# tinybord.net
KiCad netlist of a schematic drawn in Altium Designer
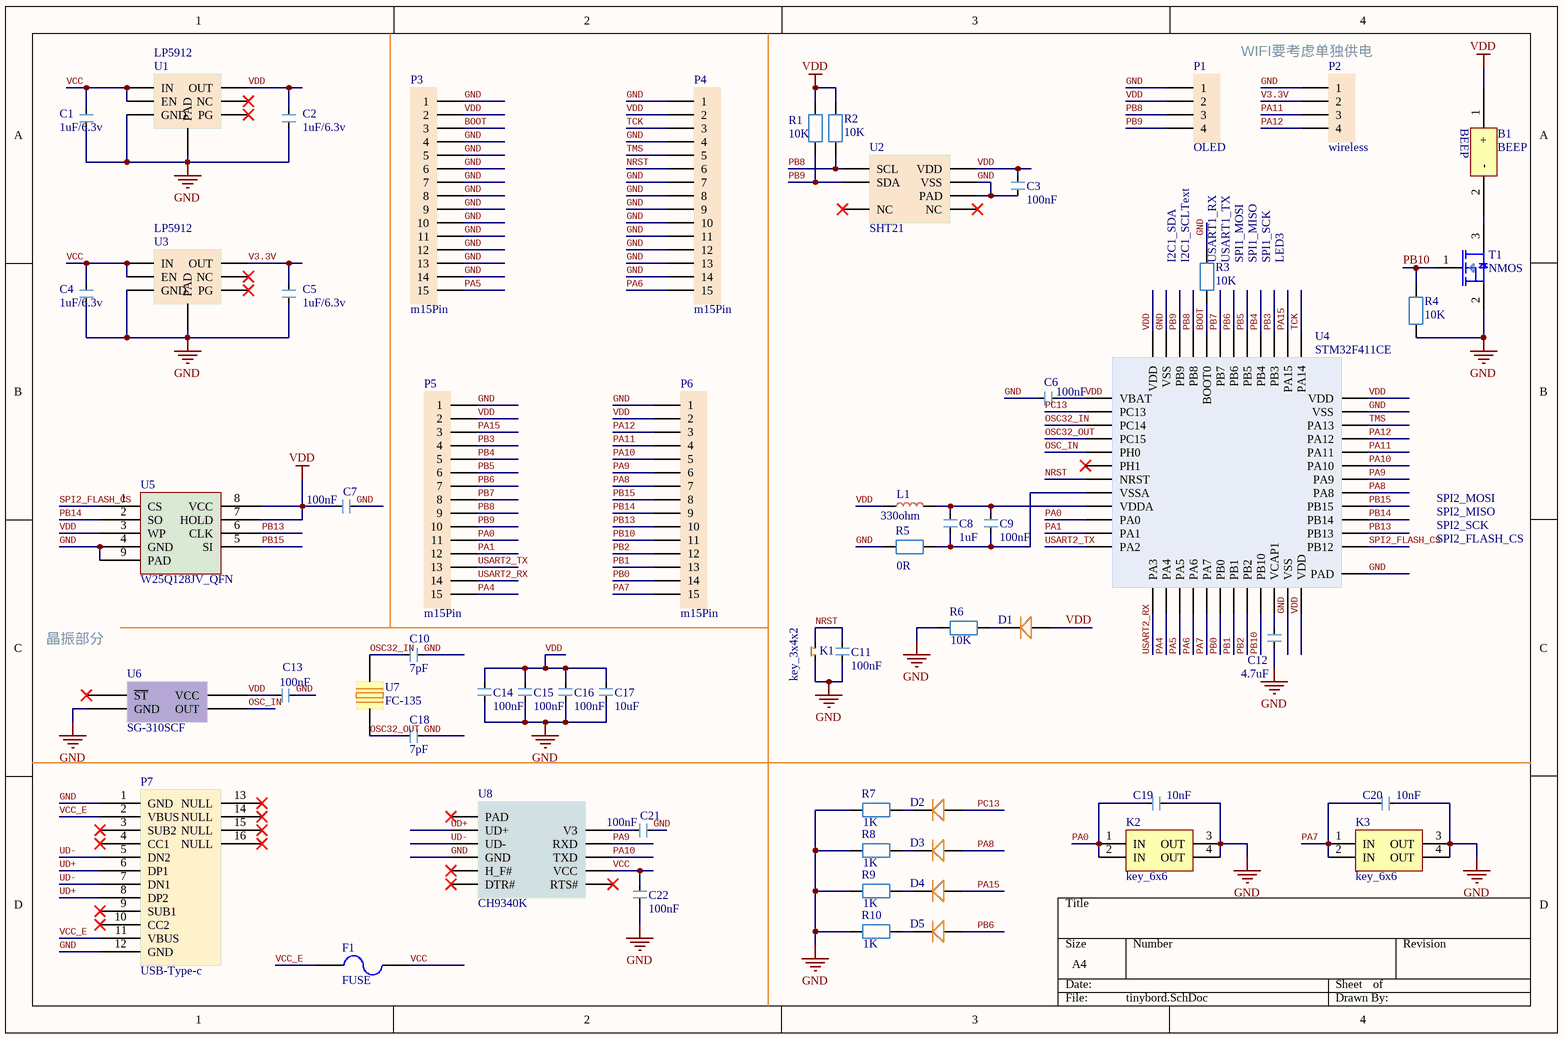
[diagram p0: tinybord.SchDoc]

(export (version "E")
  (design (tool "Eeschema 10.0.6"))
  (components
    (comp (ref "B1")
      (value "BEEP")
      (footprint "BEEP0905")
      (description "12*6")
      (libsource (lib "DemoSchlib") (part "BEEP"))
    )
    (comp (ref "C1")
      (value "1uF/6.3v")
      (footprint "C0603")
      (description "陶瓷电容")
      (fields (field (name "Comment") "C0603"))
      (libsource (lib "DemoSchlib") (part "C0603"))
    )
    (comp (ref "C2")
      (value "1uF/6.3v")
      (footprint "C0603")
      (description "陶瓷电容")
      (fields (field (name "Comment") "C0603"))
      (libsource (lib "DemoSchlib") (part "C0603"))
    )
    (comp (ref "C3")
      (value "100nF")
      (footprint "C0603")
      (description "陶瓷电容")
      (fields (field (name "Comment") "C0603"))
      (libsource (lib "DemoSchlib") (part "C0603"))
    )
    (comp (ref "C4")
      (value "1uF/6.3v")
      (footprint "C0603")
      (description "陶瓷电容")
      (fields (field (name "Comment") "C0603"))
      (libsource (lib "DemoSchlib") (part "C0603"))
    )
    (comp (ref "C5")
      (value "1uF/6.3v")
      (footprint "C0603")
      (description "陶瓷电容")
      (fields (field (name "Comment") "C0603"))
      (libsource (lib "DemoSchlib") (part "C0603"))
    )
    (comp (ref "C6")
      (value "100nF")
      (footprint "C0603")
      (description "陶瓷电容")
      (fields (field (name "Comment") "C0603"))
      (libsource (lib "DemoSchlib") (part "C0603"))
    )
    (comp (ref "C7")
      (value "100nF")
      (footprint "C0603")
      (description "陶瓷电容")
      (fields (field (name "Comment") "C0603"))
      (libsource (lib "DemoSchlib") (part "C0603"))
    )
    (comp (ref "C8")
      (value "1uF")
      (footprint "C0603")
      (description "陶瓷电容")
      (fields (field (name "Comment") "C0603"))
      (libsource (lib "DemoSchlib") (part "C0603"))
    )
    (comp (ref "C9")
      (value "100nF")
      (footprint "C0603")
      (description "陶瓷电容")
      (fields (field (name "Comment") "C0603"))
      (libsource (lib "DemoSchlib") (part "C0603"))
    )
    (comp (ref "C10")
      (value "7pF")
      (footprint "C0603")
      (description "陶瓷电容")
      (fields (field (name "Comment") "C0603"))
      (libsource (lib "DemoSchlib") (part "C0603"))
    )
    (comp (ref "C11")
      (value "100nF")
      (footprint "C0603")
      (description "陶瓷电容")
      (fields (field (name "Comment") "C0603"))
      (libsource (lib "DemoSchlib") (part "C0603"))
    )
    (comp (ref "C12")
      (value "4.7uF")
      (footprint "C0603")
      (description "陶瓷电容")
      (fields (field (name "Comment") "C0603"))
      (libsource (lib "DemoSchlib") (part "C0603"))
    )
    (comp (ref "C13")
      (value "100nF")
      (footprint "C0603")
      (description "陶瓷电容")
      (fields (field (name "Comment") "C0603"))
      (libsource (lib "DemoSchlib") (part "C0603"))
    )
    (comp (ref "C14")
      (value "100nF")
      (footprint "C0603")
      (description "陶瓷电容")
      (fields (field (name "Comment") "C0603"))
      (libsource (lib "DemoSchlib") (part "C0603"))
    )
    (comp (ref "C15")
      (value "100nF")
      (footprint "C0603")
      (description "陶瓷电容")
      (fields (field (name "Comment") "C0603"))
      (libsource (lib "DemoSchlib") (part "C0603"))
    )
    (comp (ref "C16")
      (value "100nF")
      (footprint "C0603")
      (description "陶瓷电容")
      (fields (field (name "Comment") "C0603"))
      (libsource (lib "DemoSchlib") (part "C0603"))
    )
    (comp (ref "C17")
      (value "10uF")
      (footprint "C0603")
      (description "陶瓷电容")
      (fields (field (name "Comment") "C0603"))
      (libsource (lib "DemoSchlib") (part "C0603"))
    )
    (comp (ref "C18")
      (value "7pF")
      (footprint "C0603")
      (description "陶瓷电容")
      (fields (field (name "Comment") "C0603"))
      (libsource (lib "DemoSchlib") (part "C0603"))
    )
    (comp (ref "C19")
      (value "10nF")
      (footprint "C0603")
      (description "陶瓷电容")
      (fields (field (name "Comment") "C0603"))
      (libsource (lib "DemoSchlib") (part "C0603"))
    )
    (comp (ref "C20")
      (value "10nF")
      (footprint "C0603")
      (description "陶瓷电容")
      (fields (field (name "Comment") "C0603"))
      (libsource (lib "DemoSchlib") (part "C0603"))
    )
    (comp (ref "C21")
      (value "100nF")
      (footprint "C0603")
      (description "陶瓷电容")
      (fields (field (name "Comment") "C0603"))
      (libsource (lib "DemoSchlib") (part "C0603"))
    )
    (comp (ref "C22")
      (value "100nF")
      (footprint "C0603")
      (description "陶瓷电容")
      (fields (field (name "Comment") "C0603"))
      (libsource (lib "DemoSchlib") (part "C0603"))
    )
    (comp (ref "D1")
      (value "L0603")
      (footprint "led0603")
      (description "LED")
      (libsource (lib "DemoSchlib") (part "L0603"))
    )
    (comp (ref "D2")
      (value "L0603")
      (footprint "led0603")
      (description "LED")
      (libsource (lib "DemoSchlib") (part "L0603"))
    )
    (comp (ref "D3")
      (value "L0603")
      (footprint "led0603")
      (description "LED")
      (libsource (lib "DemoSchlib") (part "L0603"))
    )
    (comp (ref "D4")
      (value "L0603")
      (footprint "led0603")
      (description "LED")
      (libsource (lib "DemoSchlib") (part "L0603"))
    )
    (comp (ref "D5")
      (value "L0603")
      (footprint "led0603")
      (description "LED")
      (libsource (lib "DemoSchlib") (part "L0603"))
    )
    (comp (ref "F1")
      (value "FUSE")
      (footprint "R0603")
      (description "PTC 1812")
      (libsource (lib "DemoSchlib") (part "PTC0603"))
    )
    (comp (ref "K1")
      (value "key_3x4x2")
      (footprint "Key 3x4x2")
      (description "贴片按键")
      (libsource (lib "DemoSchlib") (part "key_3x4x2"))
    )
    (comp (ref "K2")
      (value "key_6x6")
      (footprint "Key 6x6")
      (description "贴片按键")
      (libsource (lib "DemoSchlib") (part "key_6x6"))
    )
    (comp (ref "K3")
      (value "key_6x6")
      (footprint "Key 6x6")
      (description "贴片按键")
      (libsource (lib "DemoSchlib") (part "key_6x6"))
    )
    (comp (ref "L1")
      (value "330ohm")
      (footprint "B0603")
      (description "磁珠")
      (fields (field (name "Comment") "B0603"))
      (libsource (lib "DemoSchlib") (part "B0603"))
    )
    (comp (ref "P1")
      (value "OLED")
      (footprint "4x1 header")
      (description "1x4pin 1.27mm")
      (libsource (lib "DemoSchlib") (part "m4Pin"))
    )
    (comp (ref "P2")
      (value "wireless")
      (footprint "4x1 header")
      (description "1x4pin 1.27mm")
      (libsource (lib "DemoSchlib") (part "m4Pin"))
    )
    (comp (ref "P3")
      (value "m15Pin")
      (footprint "15x1 header")
      (description "1x4pin 1.27mm")
      (libsource (lib "DemoSchlib") (part "m15Pin"))
    )
    (comp (ref "P4")
      (value "m15Pin")
      (footprint "15x1 header")
      (description "1x4pin 1.27mm")
      (libsource (lib "") (part "m15Pin_1"))
    )
    (comp (ref "P5")
      (value "m15Pin")
      (footprint "15x1 header")
      (description "1x4pin 1.27mm")
      (libsource (lib "DemoSchlib") (part "m15Pin"))
    )
    (comp (ref "P6")
      (value "m15Pin")
      (footprint "15x1 header")
      (description "1x4pin 1.27mm")
      (libsource (lib "") (part "m15Pin_1"))
    )
    (comp (ref "P7")
      (value "USB-Type-c")
      (footprint "USB-TYPE-C")
      (description "use typec 16p")
      (libsource (lib "DemoSchlib") (part "USB-Type-c"))
    )
    (comp (ref "R1")
      (value "10K")
      (footprint "R0603")
      (description "电阻")
      (fields (field (name "Comment") "R0603"))
      (libsource (lib "DemoSchlib") (part "R0603"))
    )
    (comp (ref "R2")
      (value "10K")
      (footprint "R0603")
      (description "电阻")
      (fields (field (name "Comment") "R0603"))
      (libsource (lib "DemoSchlib") (part "R0603"))
    )
    (comp (ref "R3")
      (value "10K")
      (footprint "R0603")
      (description "电阻")
      (fields (field (name "Comment") "R0603"))
      (libsource (lib "DemoSchlib") (part "R0603"))
    )
    (comp (ref "R4")
      (value "10K")
      (footprint "R0603")
      (description "电阻")
      (fields (field (name "Comment") "R0603"))
      (libsource (lib "DemoSchlib") (part "R0603"))
    )
    (comp (ref "R5")
      (value "0R")
      (footprint "R0603")
      (description "电阻")
      (fields (field (name "Comment") "R0603"))
      (libsource (lib "DemoSchlib") (part "R0603"))
    )
    (comp (ref "R6")
      (value "10K")
      (footprint "R0603")
      (description "电阻")
      (fields (field (name "Comment") "R0603"))
      (libsource (lib "DemoSchlib") (part "R0603"))
    )
    (comp (ref "R7")
      (value "1K")
      (footprint "R0603")
      (description "电阻")
      (fields (field (name "Comment") "R0603"))
      (libsource (lib "DemoSchlib") (part "R0603"))
    )
    (comp (ref "R8")
      (value "1K")
      (footprint "R0603")
      (description "电阻")
      (fields (field (name "Comment") "R0603"))
      (libsource (lib "DemoSchlib") (part "R0603"))
    )
    (comp (ref "R9")
      (value "1K")
      (footprint "R0603")
      (description "电阻")
      (fields (field (name "Comment") "R0603"))
      (libsource (lib "DemoSchlib") (part "R0603"))
    )
    (comp (ref "R10")
      (value "1K")
      (footprint "R0603")
      (description "电阻")
      (fields (field (name "Comment") "R0603"))
      (libsource (lib "DemoSchlib") (part "R0603"))
    )
    (comp (ref "T1")
      (value "NMOS")
      (footprint "NMOS-BSH103")
      (description "infineon P-Chanel")
      (libsource (lib "DemoSchlib") (part "NMOS-BSH103"))
    )
    (comp (ref "U1")
      (value "LP5912")
      (footprint "LP5912")
      (description "LDO")
      (libsource (lib "DemoSchlib") (part "LP5912"))
    )
    (comp (ref "U2")
      (value "SHT21")
      (footprint "SHT21")
      (description "温湿度传感器")
      (libsource (lib "DemoSchlib") (part "SHT21"))
    )
    (comp (ref "U3")
      (value "LP5912")
      (footprint "LP5912")
      (description "LDO")
      (libsource (lib "DemoSchlib") (part "LP5912"))
    )
    (comp (ref "U4")
      (value "STM32F411CE")
      (footprint "STM32F411CE QFN")
      (description "STM32F411 QFN48PIN")
      (libsource (lib "DemoSchlib") (part "STM32F411CE"))
    )
    (comp (ref "U5")
      (value "W25Q128JV_QFN")
      (footprint "W25Q64 QFN")
      (description "flash")
      (libsource (lib "DemoSchlib") (part "W25Q128JV_QFN"))
    )
    (comp (ref "U6")
      (value "SG-310SCF")
      (footprint "SG-310SCF")
      (description "有源晶振3225")
      (libsource (lib "DemoSchlib") (part "SG-310SCF"))
    )
    (comp (ref "U7")
      (value "FC-135")
      (footprint "FC-135")
      (description "32.768K无源晶振")
      (libsource (lib "DemoSchlib") (part "FC-135"))
    )
    (comp (ref "U8")
      (value "CH9340K")
      (footprint "CH9340")
      (description "USB转串口")
      (libsource (lib "DemoSchlib") (part "CH9340K"))
    )
  )
  (nets
    (net (code "1") (name "/BOOT") (class "Default")
      (node (ref "P3") (pin "3") (pinfunction "3_3") (pintype "passive"))
      (node (ref "R3") (pin "1") (pintype "passive"))
      (node (ref "U4") (pin "44") (pinfunction "BOOT0_44") (pintype "passive"))
    )
    (net (code "2") (name "/NRST") (class "Default")
      (node (ref "C11") (pin "2") (pintype "passive"))
      (node (ref "K1") (pin "2") (pintype "passive"))
      (node (ref "P4") (pin "6") (pinfunction "6_6") (pintype "passive"))
      (node (ref "U4") (pin "7") (pinfunction "NRST_7") (pintype "passive"))
    )
    (net (code "3") (name "/OSC32_IN") (class "Default")
      (node (ref "C10") (pin "2") (pintype "passive"))
      (node (ref "U4") (pin "3") (pinfunction "PC14_3") (pintype "passive"))
      (node (ref "U7") (pin "2") (pintype "passive"))
    )
    (net (code "4") (name "/OSC32_OUT") (class "Default")
      (node (ref "C18") (pin "2") (pintype "passive"))
      (node (ref "U4") (pin "4") (pinfunction "PC15_4") (pintype "passive"))
      (node (ref "U7") (pin "1") (pintype "passive"))
    )
    (net (code "5") (name "/OSC_IN") (class "Default")
      (node (ref "U4") (pin "5") (pinfunction "PH0_5") (pintype "passive"))
      (node (ref "U6") (pin "3") (pinfunction "OUT_3") (pintype "passive"))
    )
    (net (code "6") (name "/PA0") (class "Default")
      (node (ref "C19") (pin "2") (pintype "passive"))
      (node (ref "K2") (pin "1") (pinfunction "IN_1") (pintype "passive"))
      (node (ref "K2") (pin "2") (pinfunction "IN_2") (pintype "passive"))
      (node (ref "P5") (pin "11") (pinfunction "11_11") (pintype "passive"))
      (node (ref "U4") (pin "10") (pinfunction "PA0_10") (pintype "passive"))
    )
    (net (code "7") (name "/PA1") (class "Default")
      (node (ref "P5") (pin "12") (pinfunction "12_12") (pintype "passive"))
      (node (ref "U4") (pin "11") (pinfunction "PA1_11") (pintype "passive"))
    )
    (net (code "8") (name "/PA4") (class "Default")
      (node (ref "P5") (pin "15") (pinfunction "15_15") (pintype "passive"))
      (node (ref "U4") (pin "14") (pinfunction "PA4_14") (pintype "passive"))
    )
    (net (code "9") (name "/PA5") (class "Default")
      (node (ref "P3") (pin "15") (pinfunction "15_15") (pintype "passive"))
      (node (ref "U4") (pin "15") (pinfunction "PA5_15") (pintype "passive"))
    )
    (net (code "10") (name "/PA6") (class "Default")
      (node (ref "P4") (pin "15") (pinfunction "15_15") (pintype "passive"))
      (node (ref "U4") (pin "16") (pinfunction "PA6_16") (pintype "passive"))
    )
    (net (code "11") (name "/PA7") (class "Default")
      (node (ref "C20") (pin "2") (pintype "passive"))
      (node (ref "K3") (pin "1") (pinfunction "IN_1") (pintype "passive"))
      (node (ref "K3") (pin "2") (pinfunction "IN_2") (pintype "passive"))
      (node (ref "P6") (pin "15") (pinfunction "15_15") (pintype "passive"))
      (node (ref "U4") (pin "17") (pinfunction "PA7_17") (pintype "passive"))
    )
    (net (code "12") (name "/PA8") (class "Default")
      (node (ref "D3") (pin "2") (pintype "passive"))
      (node (ref "P6") (pin "7") (pinfunction "7_7") (pintype "passive"))
      (node (ref "U4") (pin "29") (pinfunction "PA8_29") (pintype "passive"))
    )
    (net (code "13") (name "/PA9") (class "Default")
      (node (ref "P6") (pin "6") (pinfunction "6_6") (pintype "passive"))
      (node (ref "U4") (pin "30") (pinfunction "PA9_30") (pintype "passive"))
      (node (ref "U8") (pin "9") (pinfunction "RXD_9") (pintype "passive"))
    )
    (net (code "14") (name "/PA10") (class "Default")
      (node (ref "P6") (pin "5") (pinfunction "5_5") (pintype "passive"))
      (node (ref "U4") (pin "31") (pinfunction "PA10_31") (pintype "passive"))
      (node (ref "U8") (pin "8") (pinfunction "TXD_8") (pintype "passive"))
    )
    (net (code "15") (name "/PA11") (class "Default")
      (node (ref "P2") (pin "3") (pinfunction "3_3") (pintype "passive"))
      (node (ref "P6") (pin "4") (pinfunction "4_4") (pintype "passive"))
      (node (ref "U4") (pin "32") (pinfunction "PA11_32") (pintype "passive"))
    )
    (net (code "16") (name "/PA12") (class "Default")
      (node (ref "P2") (pin "4") (pinfunction "4_4") (pintype "passive"))
      (node (ref "P6") (pin "3") (pinfunction "3_3") (pintype "passive"))
      (node (ref "U4") (pin "33") (pinfunction "PA12_33") (pintype "passive"))
    )
    (net (code "17") (name "/PA15") (class "Default")
      (node (ref "D4") (pin "2") (pintype "passive"))
      (node (ref "P5") (pin "3") (pinfunction "3_3") (pintype "passive"))
      (node (ref "U4") (pin "38") (pinfunction "PA15_38") (pintype "passive"))
    )
    (net (code "18") (name "/PB0") (class "Default")
      (node (ref "P6") (pin "14") (pinfunction "14_14") (pintype "passive"))
      (node (ref "U4") (pin "18") (pinfunction "PB0_18") (pintype "passive"))
    )
    (net (code "19") (name "/PB1") (class "Default")
      (node (ref "P6") (pin "13") (pinfunction "13_13") (pintype "passive"))
      (node (ref "U4") (pin "19") (pinfunction "PB1_19") (pintype "passive"))
    )
    (net (code "20") (name "/PB2") (class "Default")
      (node (ref "P6") (pin "12") (pinfunction "12_12") (pintype "passive"))
      (node (ref "U4") (pin "20") (pinfunction "PB2_20") (pintype "passive"))
    )
    (net (code "21") (name "/PB3") (class "Default")
      (node (ref "P5") (pin "4") (pinfunction "4_4") (pintype "passive"))
      (node (ref "U4") (pin "39") (pinfunction "PB3_39") (pintype "passive"))
    )
    (net (code "22") (name "/PB4") (class "Default")
      (node (ref "P5") (pin "5") (pinfunction "5_5") (pintype "passive"))
      (node (ref "U4") (pin "40") (pinfunction "PB4_40") (pintype "passive"))
    )
    (net (code "23") (name "/PB5") (class "Default")
      (node (ref "P5") (pin "6") (pinfunction "6_6") (pintype "passive"))
      (node (ref "U4") (pin "41") (pinfunction "PB5_41") (pintype "passive"))
    )
    (net (code "24") (name "/PB6") (class "Default")
      (node (ref "D5") (pin "2") (pintype "passive"))
      (node (ref "P5") (pin "7") (pinfunction "7_7") (pintype "passive"))
      (node (ref "U4") (pin "42") (pinfunction "PB6_42") (pintype "passive"))
    )
    (net (code "25") (name "/PB7") (class "Default")
      (node (ref "P5") (pin "8") (pinfunction "8_8") (pintype "passive"))
      (node (ref "U4") (pin "43") (pinfunction "PB7_43") (pintype "passive"))
    )
    (net (code "26") (name "/PB8") (class "Default")
      (node (ref "P1") (pin "3") (pinfunction "3_3") (pintype "passive"))
      (node (ref "P5") (pin "9") (pinfunction "9_9") (pintype "passive"))
      (node (ref "R2") (pin "1") (pintype "passive"))
      (node (ref "U2") (pin "6") (pinfunction "SCL_6") (pintype "passive"))
      (node (ref "U4") (pin "45") (pinfunction "PB8_45") (pintype "passive"))
    )
    (net (code "27") (name "/PB9") (class "Default")
      (node (ref "P1") (pin "4") (pinfunction "4_4") (pintype "passive"))
      (node (ref "P5") (pin "10") (pinfunction "10_10") (pintype "passive"))
      (node (ref "R1") (pin "1") (pintype "passive"))
      (node (ref "U2") (pin "1") (pinfunction "SDA_1") (pintype "passive"))
      (node (ref "U4") (pin "46") (pinfunction "PB9_46") (pintype "passive"))
    )
    (net (code "28") (name "/PB10") (class "Default")
      (node (ref "P6") (pin "11") (pinfunction "11_11") (pintype "passive"))
      (node (ref "R4") (pin "2") (pintype "passive"))
      (node (ref "T1") (pin "1") (pinfunction "G_1") (pintype "passive"))
      (node (ref "U4") (pin "21") (pinfunction "PB10_21") (pintype "passive"))
    )
    (net (code "29") (name "/PB13") (class "Default")
      (node (ref "P6") (pin "10") (pinfunction "10_10") (pintype "passive"))
      (node (ref "U4") (pin "26") (pinfunction "PB13_26") (pintype "passive"))
      (node (ref "U5") (pin "6") (pinfunction "CLK_6") (pintype "passive"))
    )
    (net (code "30") (name "/PB14") (class "Default")
      (node (ref "P6") (pin "9") (pinfunction "9_9") (pintype "passive"))
      (node (ref "U4") (pin "27") (pinfunction "PB14_27") (pintype "passive"))
      (node (ref "U5") (pin "2") (pinfunction "SO_2") (pintype "passive"))
    )
    (net (code "31") (name "/PB15") (class "Default")
      (node (ref "P6") (pin "8") (pinfunction "8_8") (pintype "passive"))
      (node (ref "U4") (pin "28") (pinfunction "PB15_28") (pintype "passive"))
      (node (ref "U5") (pin "5") (pinfunction "SI_5") (pintype "passive"))
    )
    (net (code "32") (name "/PC13") (class "Default")
      (node (ref "D2") (pin "2") (pintype "passive"))
      (node (ref "U4") (pin "2") (pinfunction "PC13_2") (pintype "passive"))
    )
    (net (code "33") (name "/SPI2_FLASH_CS") (class "Default")
      (node (ref "U4") (pin "25") (pinfunction "PB12_25") (pintype "passive"))
      (node (ref "U5") (pin "1") (pinfunction "CS_1") (pintype "passive"))
    )
    (net (code "34") (name "/TCK") (class "Default")
      (node (ref "P4") (pin "3") (pinfunction "3_3") (pintype "passive"))
      (node (ref "U4") (pin "37") (pinfunction "PA14_37") (pintype "passive"))
    )
    (net (code "35") (name "/TMS") (class "Default")
      (node (ref "P4") (pin "5") (pinfunction "5_5") (pintype "passive"))
      (node (ref "U4") (pin "34") (pinfunction "PA13_34") (pintype "passive"))
    )
    (net (code "36") (name "/UD+") (class "Default")
      (node (ref "P7") (pin "6") (pinfunction "DP1_6") (pintype "passive"))
      (node (ref "P7") (pin "8") (pinfunction "DP2_8") (pintype "passive"))
      (node (ref "U8") (pin "1") (pinfunction "UD+_1") (pintype "passive"))
    )
    (net (code "37") (name "/UD-") (class "Default")
      (node (ref "P7") (pin "5") (pinfunction "DN2_5") (pintype "passive"))
      (node (ref "P7") (pin "7") (pinfunction "DN1_7") (pintype "passive"))
      (node (ref "U8") (pin "2") (pinfunction "UD-_2") (pintype "passive"))
    )
    (net (code "38") (name "/USART2_RX") (class "Default")
      (node (ref "P5") (pin "14") (pinfunction "14_14") (pintype "passive"))
      (node (ref "U4") (pin "13") (pinfunction "PA3_13") (pintype "passive"))
    )
    (net (code "39") (name "/USART2_TX") (class "Default")
      (node (ref "P5") (pin "13") (pinfunction "13_13") (pintype "passive"))
      (node (ref "U4") (pin "12") (pinfunction "PA2_12") (pintype "passive"))
    )
    (net (code "40") (name "/V3.3V") (class "Default")
      (node (ref "C5") (pin "2") (pintype "passive"))
      (node (ref "P2") (pin "2") (pinfunction "2_2") (pintype "passive"))
      (node (ref "U3") (pin "1") (pinfunction "OUT_1") (pintype "passive"))
    )
    (net (code "41") (name "/VCC") (class "Default")
      (node (ref "C1") (pin "2") (pintype "passive"))
      (node (ref "C22") (pin "2") (pintype "passive"))
      (node (ref "C4") (pin "2") (pintype "passive"))
      (node (ref "F1") (pin "2") (pinfunction "2_2") (pintype "passive"))
      (node (ref "U1") (pin "4") (pinfunction "EN_4") (pintype "passive"))
      (node (ref "U1") (pin "6") (pinfunction "IN_6") (pintype "passive"))
      (node (ref "U3") (pin "4") (pinfunction "EN_4") (pintype "passive"))
      (node (ref "U3") (pin "6") (pinfunction "IN_6") (pintype "passive"))
      (node (ref "U8") (pin "7") (pinfunction "VCC_7") (pintype "passive"))
    )
    (net (code "42") (name "/VCC_E") (class "Default")
      (node (ref "F1") (pin "1") (pinfunction "1_1") (pintype "passive"))
      (node (ref "P7") (pin "11") (pinfunction "VBUS_11") (pintype "passive"))
      (node (ref "P7") (pin "2") (pinfunction "VBUS_2") (pintype "passive"))
    )
    (net (code "43") (name "GND") (class "Default")
      (node (ref "C1") (pin "1") (pintype "passive"))
      (node (ref "C10") (pin "1") (pintype "passive"))
      (node (ref "C11") (pin "1") (pintype "passive"))
      (node (ref "C12") (pin "1") (pintype "passive"))
      (node (ref "C13") (pin "2") (pintype "passive"))
      (node (ref "C14") (pin "1") (pintype "passive"))
      (node (ref "C15") (pin "1") (pintype "passive"))
      (node (ref "C16") (pin "1") (pintype "passive"))
      (node (ref "C17") (pin "1") (pintype "passive"))
      (node (ref "C18") (pin "1") (pintype "passive"))
      (node (ref "C19") (pin "1") (pintype "passive"))
      (node (ref "C2") (pin "1") (pintype "passive"))
      (node (ref "C20") (pin "1") (pintype "passive"))
      (node (ref "C21") (pin "2") (pintype "passive"))
      (node (ref "C22") (pin "1") (pintype "passive"))
      (node (ref "C3") (pin "1") (pintype "passive"))
      (node (ref "C4") (pin "1") (pintype "passive"))
      (node (ref "C5") (pin "1") (pintype "passive"))
      (node (ref "C6") (pin "1") (pintype "passive"))
      (node (ref "C7") (pin "2") (pintype "passive"))
      (node (ref "K1") (pin "1") (pintype "passive"))
      (node (ref "K2") (pin "3") (pinfunction "OUT_3") (pintype "passive"))
      (node (ref "K2") (pin "4") (pinfunction "OUT_4") (pintype "passive"))
      (node (ref "K3") (pin "3") (pinfunction "OUT_3") (pintype "passive"))
      (node (ref "K3") (pin "4") (pinfunction "OUT_4") (pintype "passive"))
      (node (ref "P1") (pin "1") (pinfunction "1_1") (pintype "passive"))
      (node (ref "P2") (pin "1") (pinfunction "1_1") (pintype "passive"))
      (node (ref "P3") (pin "1") (pinfunction "1_1") (pintype "passive"))
      (node (ref "P3") (pin "10") (pinfunction "10_10") (pintype "passive"))
      (node (ref "P3") (pin "11") (pinfunction "11_11") (pintype "passive"))
      (node (ref "P3") (pin "12") (pinfunction "12_12") (pintype "passive"))
      (node (ref "P3") (pin "13") (pinfunction "13_13") (pintype "passive"))
      (node (ref "P3") (pin "14") (pinfunction "14_14") (pintype "passive"))
      (node (ref "P3") (pin "4") (pinfunction "4_4") (pintype "passive"))
      (node (ref "P3") (pin "5") (pinfunction "5_5") (pintype "passive"))
      (node (ref "P3") (pin "6") (pinfunction "6_6") (pintype "passive"))
      (node (ref "P3") (pin "7") (pinfunction "7_7") (pintype "passive"))
      (node (ref "P3") (pin "8") (pinfunction "8_8") (pintype "passive"))
      (node (ref "P3") (pin "9") (pinfunction "9_9") (pintype "passive"))
      (node (ref "P4") (pin "1") (pinfunction "1_1") (pintype "passive"))
      (node (ref "P4") (pin "10") (pinfunction "10_10") (pintype "passive"))
      (node (ref "P4") (pin "11") (pinfunction "11_11") (pintype "passive"))
      (node (ref "P4") (pin "12") (pinfunction "12_12") (pintype "passive"))
      (node (ref "P4") (pin "13") (pinfunction "13_13") (pintype "passive"))
      (node (ref "P4") (pin "14") (pinfunction "14_14") (pintype "passive"))
      (node (ref "P4") (pin "4") (pinfunction "4_4") (pintype "passive"))
      (node (ref "P4") (pin "7") (pinfunction "7_7") (pintype "passive"))
      (node (ref "P4") (pin "8") (pinfunction "8_8") (pintype "passive"))
      (node (ref "P4") (pin "9") (pinfunction "9_9") (pintype "passive"))
      (node (ref "P5") (pin "1") (pinfunction "1_1") (pintype "passive"))
      (node (ref "P6") (pin "1") (pinfunction "1_1") (pintype "passive"))
      (node (ref "P7") (pin "1") (pinfunction "GND_1") (pintype "passive"))
      (node (ref "P7") (pin "12") (pinfunction "GND_12") (pintype "passive"))
      (node (ref "R10") (pin "1") (pintype "passive"))
      (node (ref "R3") (pin "2") (pintype "passive"))
      (node (ref "R4") (pin "1") (pintype "passive"))
      (node (ref "R5") (pin "1") (pintype "passive"))
      (node (ref "R6") (pin "1") (pintype "passive"))
      (node (ref "R7") (pin "1") (pintype "passive"))
      (node (ref "R8") (pin "1") (pintype "passive"))
      (node (ref "R9") (pin "1") (pintype "passive"))
      (node (ref "T1") (pin "2") (pinfunction "S_2") (pintype "passive"))
      (node (ref "U1") (pin "5") (pinfunction "GND_5") (pintype "passive"))
      (node (ref "U1") (pin "7") (pinfunction "PAD_7") (pintype "passive"))
      (node (ref "U2") (pin "2") (pinfunction "VSS_2") (pintype "passive"))
      (node (ref "U2") (pin "7") (pinfunction "PAD_7") (pintype "passive"))
      (node (ref "U3") (pin "5") (pinfunction "GND_5") (pintype "passive"))
      (node (ref "U3") (pin "7") (pinfunction "PAD_7") (pintype "passive"))
      (node (ref "U4") (pin "23") (pinfunction "VSS_23") (pintype "passive"))
      (node (ref "U4") (pin "35") (pinfunction "VSS_35") (pintype "passive"))
      (node (ref "U4") (pin "47") (pinfunction "VSS_47") (pintype "passive"))
      (node (ref "U4") (pin "49") (pinfunction "PAD_49") (pintype "passive"))
      (node (ref "U5") (pin "4") (pinfunction "GND_4") (pintype "passive"))
      (node (ref "U5") (pin "9") (pinfunction "PAD_9") (pintype "passive"))
      (node (ref "U6") (pin "2") (pinfunction "GND_2") (pintype "passive"))
      (node (ref "U8") (pin "3") (pinfunction "GND_3") (pintype "passive"))
    )
    (net (code "44") (name "Net-(B1--)") (class "Default")
      (node (ref "B1") (pin "2") (pinfunction "-_2") (pintype "passive"))
      (node (ref "T1") (pin "3") (pinfunction "D_3") (pintype "passive"))
    )
    (net (code "45") (name "Net-(D1-Pad1)") (class "Default")
      (node (ref "D1") (pin "1") (pintype "passive"))
      (node (ref "R6") (pin "2") (pintype "passive"))
    )
    (net (code "46") (name "Net-(D2-Pad1)") (class "Default")
      (node (ref "D2") (pin "1") (pintype "passive"))
      (node (ref "R7") (pin "2") (pintype "passive"))
    )
    (net (code "47") (name "Net-(D3-Pad1)") (class "Default")
      (node (ref "D3") (pin "1") (pintype "passive"))
      (node (ref "R8") (pin "2") (pintype "passive"))
    )
    (net (code "48") (name "Net-(D4-Pad1)") (class "Default")
      (node (ref "D4") (pin "1") (pintype "passive"))
      (node (ref "R9") (pin "2") (pintype "passive"))
    )
    (net (code "49") (name "Net-(D5-Pad1)") (class "Default")
      (node (ref "D5") (pin "1") (pintype "passive"))
      (node (ref "R10") (pin "2") (pintype "passive"))
    )
    (net (code "50") (name "Net-(U4-VCAP1)") (class "Default")
      (node (ref "C12") (pin "2") (pintype "passive"))
      (node (ref "U4") (pin "22") (pinfunction "VCAP1_22") (pintype "passive"))
    )
    (net (code "51") (name "Net-(U4-VDDA)") (class "Default")
      (node (ref "C8") (pin "2") (pintype "passive"))
      (node (ref "C9") (pin "2") (pintype "passive"))
      (node (ref "L1") (pin "2") (pintype "passive"))
      (node (ref "U4") (pin "9") (pinfunction "VDDA_9") (pintype "passive"))
    )
    (net (code "52") (name "Net-(U4-VSSA)") (class "Default")
      (node (ref "C8") (pin "1") (pintype "passive"))
      (node (ref "C9") (pin "1") (pintype "passive"))
      (node (ref "R5") (pin "2") (pintype "passive"))
      (node (ref "U4") (pin "8") (pinfunction "VSSA_8") (pintype "passive"))
    )
    (net (code "53") (name "Net-(U8-V3)") (class "Default")
      (node (ref "C21") (pin "1") (pintype "passive"))
      (node (ref "U8") (pin "10") (pinfunction "V3_10") (pintype "passive"))
    )
    (net (code "54") (name "VDD") (class "Default")
      (node (ref "B1") (pin "1") (pinfunction "+_1") (pintype "passive"))
      (node (ref "C13") (pin "1") (pintype "passive"))
      (node (ref "C14") (pin "2") (pintype "passive"))
      (node (ref "C15") (pin "2") (pintype "passive"))
      (node (ref "C16") (pin "2") (pintype "passive"))
      (node (ref "C17") (pin "2") (pintype "passive"))
      (node (ref "C2") (pin "2") (pintype "passive"))
      (node (ref "C3") (pin "2") (pintype "passive"))
      (node (ref "C6") (pin "2") (pintype "passive"))
      (node (ref "C7") (pin "1") (pintype "passive"))
      (node (ref "D1") (pin "2") (pintype "passive"))
      (node (ref "L1") (pin "1") (pintype "passive"))
      (node (ref "P1") (pin "2") (pinfunction "2_2") (pintype "passive"))
      (node (ref "P3") (pin "2") (pinfunction "2_2") (pintype "passive"))
      (node (ref "P4") (pin "2") (pinfunction "2_2") (pintype "passive"))
      (node (ref "P5") (pin "2") (pinfunction "2_2") (pintype "passive"))
      (node (ref "P6") (pin "2") (pinfunction "2_2") (pintype "passive"))
      (node (ref "R1") (pin "2") (pintype "passive"))
      (node (ref "R2") (pin "2") (pintype "passive"))
      (node (ref "U1") (pin "1") (pinfunction "OUT_1") (pintype "passive"))
      (node (ref "U2") (pin "5") (pinfunction "VDD_5") (pintype "passive"))
      (node (ref "U4") (pin "1") (pinfunction "VBAT_1") (pintype "passive"))
      (node (ref "U4") (pin "24") (pinfunction "VDD_24") (pintype "passive"))
      (node (ref "U4") (pin "36") (pinfunction "VDD_36") (pintype "passive"))
      (node (ref "U4") (pin "48") (pinfunction "VDD_48") (pintype "passive"))
      (node (ref "U5") (pin "3") (pinfunction "WP_3") (pintype "passive"))
      (node (ref "U5") (pin "7") (pinfunction "HOLD_7") (pintype "passive"))
      (node (ref "U5") (pin "8") (pinfunction "VCC_8") (pintype "passive"))
      (node (ref "U6") (pin "4") (pinfunction "VCC_4") (pintype "passive"))
    )
    (net (code "55") (name "unconnected-(P7-CC1-Pad4)") (class "Default")
      (node (ref "P7") (pin "4") (pinfunction "CC1_4") (pintype "passive+no_connect"))
    )
    (net (code "56") (name "unconnected-(P7-CC2-Pad10)") (class "Default")
      (node (ref "P7") (pin "10") (pinfunction "CC2_10") (pintype "passive+no_connect"))
    )
    (net (code "57") (name "unconnected-(P7-NULL-Pad13)") (class "Default")
      (node (ref "P7") (pin "13") (pinfunction "NULL_13") (pintype "passive+no_connect"))
    )
    (net (code "58") (name "unconnected-(P7-NULL-Pad14)") (class "Default")
      (node (ref "P7") (pin "14") (pinfunction "NULL_14") (pintype "passive+no_connect"))
    )
    (net (code "59") (name "unconnected-(P7-NULL-Pad15)") (class "Default")
      (node (ref "P7") (pin "15") (pinfunction "NULL_15") (pintype "passive+no_connect"))
    )
    (net (code "60") (name "unconnected-(P7-NULL-Pad16)") (class "Default")
      (node (ref "P7") (pin "16") (pinfunction "NULL_16") (pintype "passive+no_connect"))
    )
    (net (code "61") (name "unconnected-(P7-SUB1-Pad9)") (class "Default")
      (node (ref "P7") (pin "9") (pinfunction "SUB1_9") (pintype "passive+no_connect"))
    )
    (net (code "62") (name "unconnected-(P7-SUB2-Pad3)") (class "Default")
      (node (ref "P7") (pin "3") (pinfunction "SUB2_3") (pintype "passive+no_connect"))
    )
    (net (code "63") (name "unconnected-(U1-NC-Pad2)") (class "Default")
      (node (ref "U1") (pin "2") (pinfunction "NC_2") (pintype "passive+no_connect"))
    )
    (net (code "64") (name "unconnected-(U1-PG-Pad3)") (class "Default")
      (node (ref "U1") (pin "3") (pinfunction "PG_3") (pintype "passive+no_connect"))
    )
    (net (code "65") (name "unconnected-(U2-NC-Pad3)") (class "Default")
      (node (ref "U2") (pin "3") (pinfunction "NC_3") (pintype "passive+no_connect"))
    )
    (net (code "66") (name "unconnected-(U2-NC-Pad4)") (class "Default")
      (node (ref "U2") (pin "4") (pinfunction "NC_4") (pintype "passive+no_connect"))
    )
    (net (code "67") (name "unconnected-(U3-NC-Pad2)") (class "Default")
      (node (ref "U3") (pin "2") (pinfunction "NC_2") (pintype "passive+no_connect"))
    )
    (net (code "68") (name "unconnected-(U3-PG-Pad3)") (class "Default")
      (node (ref "U3") (pin "3") (pinfunction "PG_3") (pintype "passive+no_connect"))
    )
    (net (code "69") (name "unconnected-(U4-PH1-Pad6)") (class "Default")
      (node (ref "U4") (pin "6") (pinfunction "PH1_6") (pintype "passive+no_connect"))
    )
    (net (code "70") (name "unconnected-(U6-~{ST}-Pad1)") (class "Default")
      (node (ref "U6") (pin "1") (pinfunction "~{ST}_1") (pintype "passive+no_connect"))
    )
    (net (code "71") (name "unconnected-(U8-DTR#-Pad5)") (class "Default")
      (node (ref "U8") (pin "5") (pinfunction "DTR#_5") (pintype "passive+no_connect"))
    )
    (net (code "72") (name "unconnected-(U8-H_F#-Pad4)") (class "Default")
      (node (ref "U8") (pin "4") (pinfunction "H_F#_4") (pintype "passive+no_connect"))
    )
    (net (code "73") (name "unconnected-(U8-PAD-Pad11)") (class "Default")
      (node (ref "U8") (pin "11") (pinfunction "PAD_11") (pintype "passive+no_connect"))
    )
    (net (code "74") (name "unconnected-(U8-RTS#-Pad6)") (class "Default")
      (node (ref "U8") (pin "6") (pinfunction "RTS#_6") (pintype "passive+no_connect"))
    )
  )
)
